# 16_-_PWR_2V5_1V5.net
KiCad netlist of a schematic drawn in Altium Designer
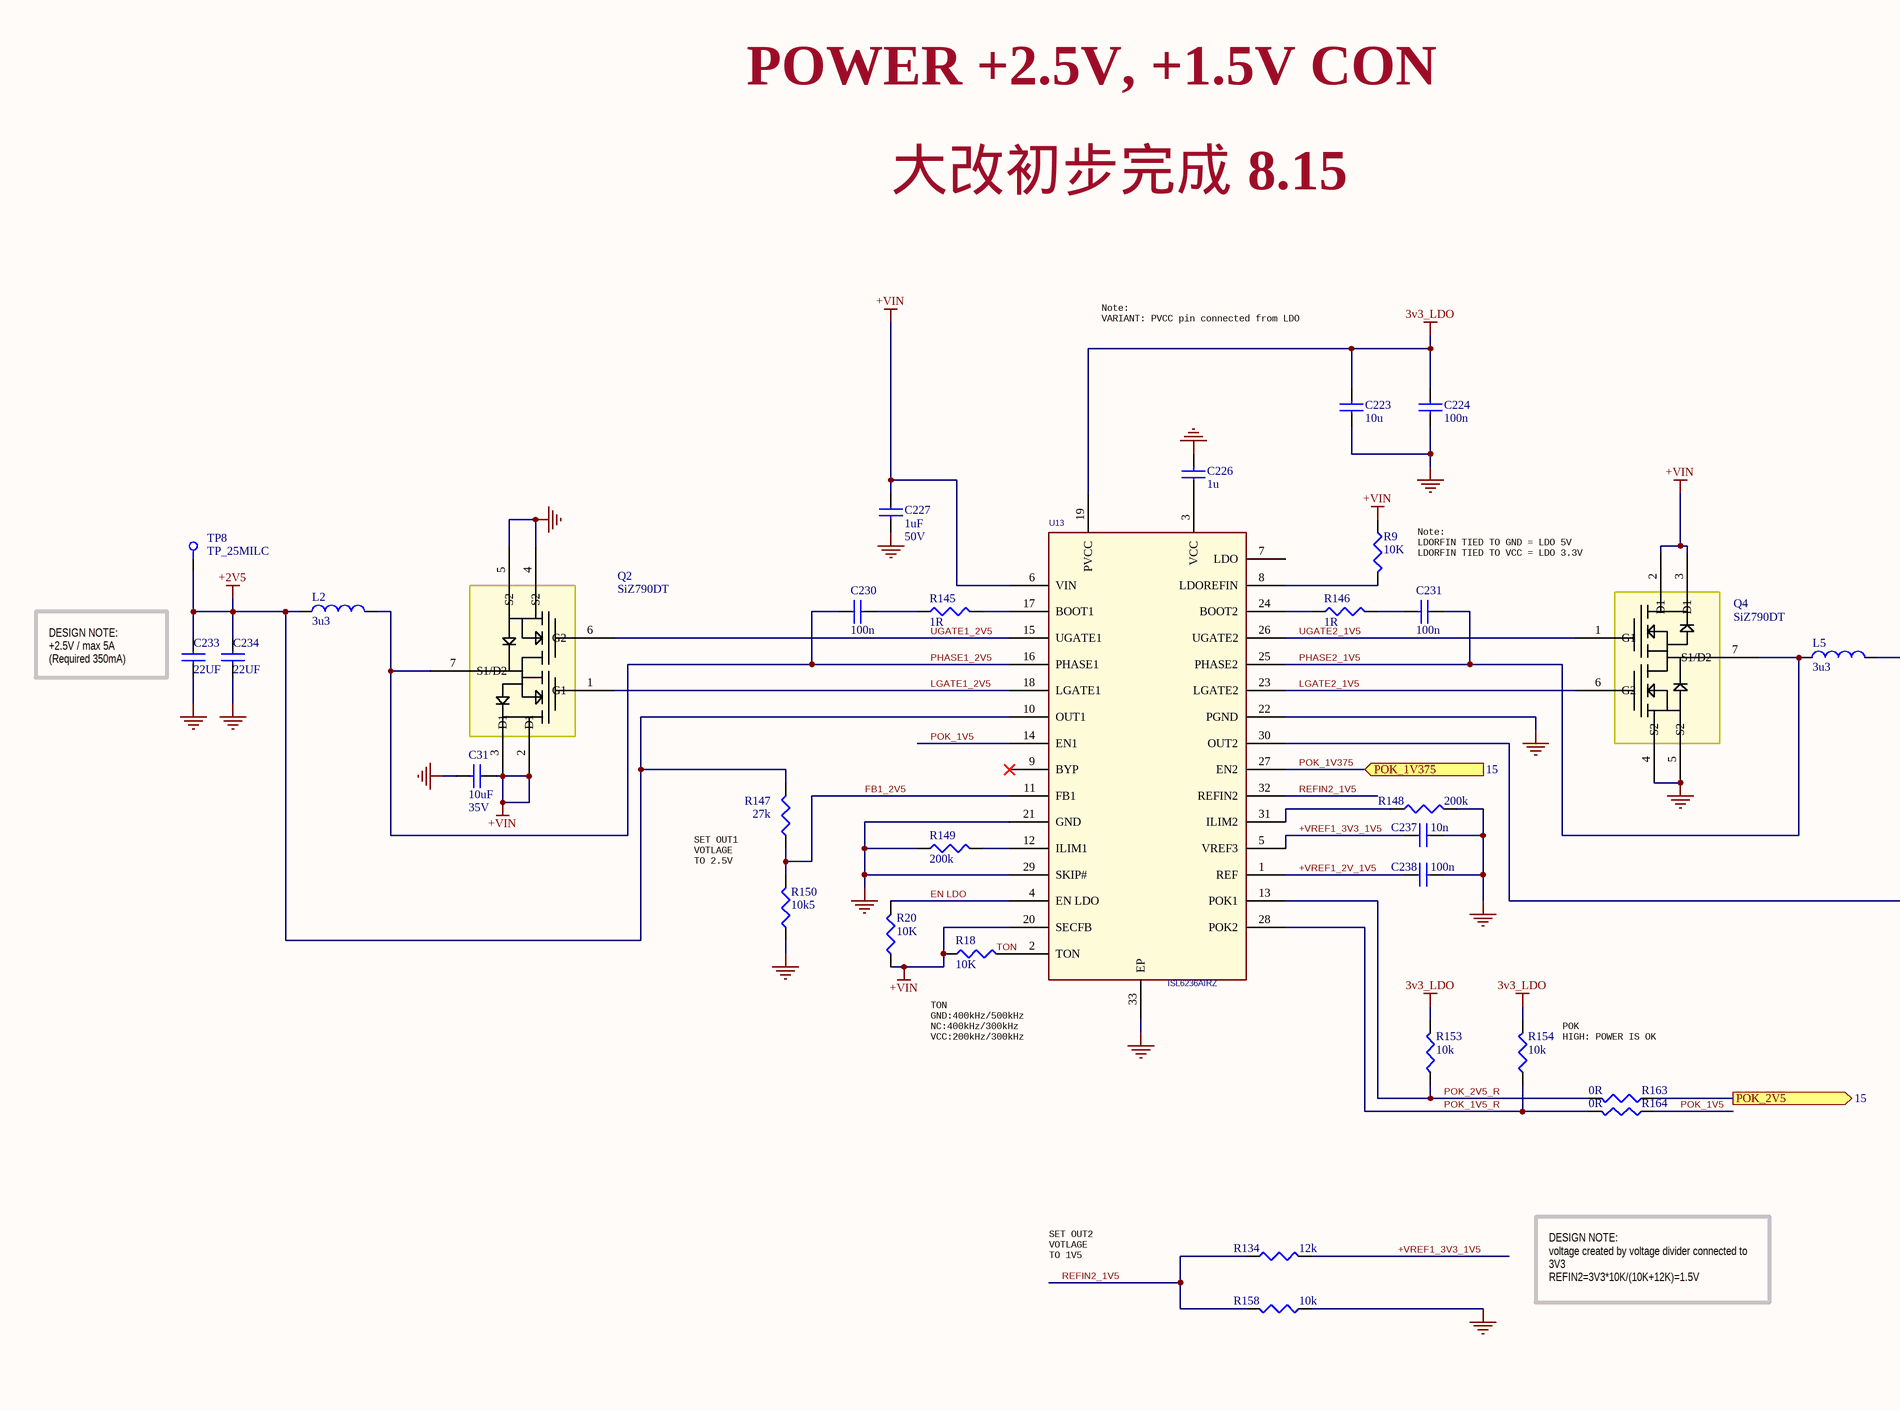
[diagram p0: [16] - PWR 2V5, 1V5.SchDoc, left]
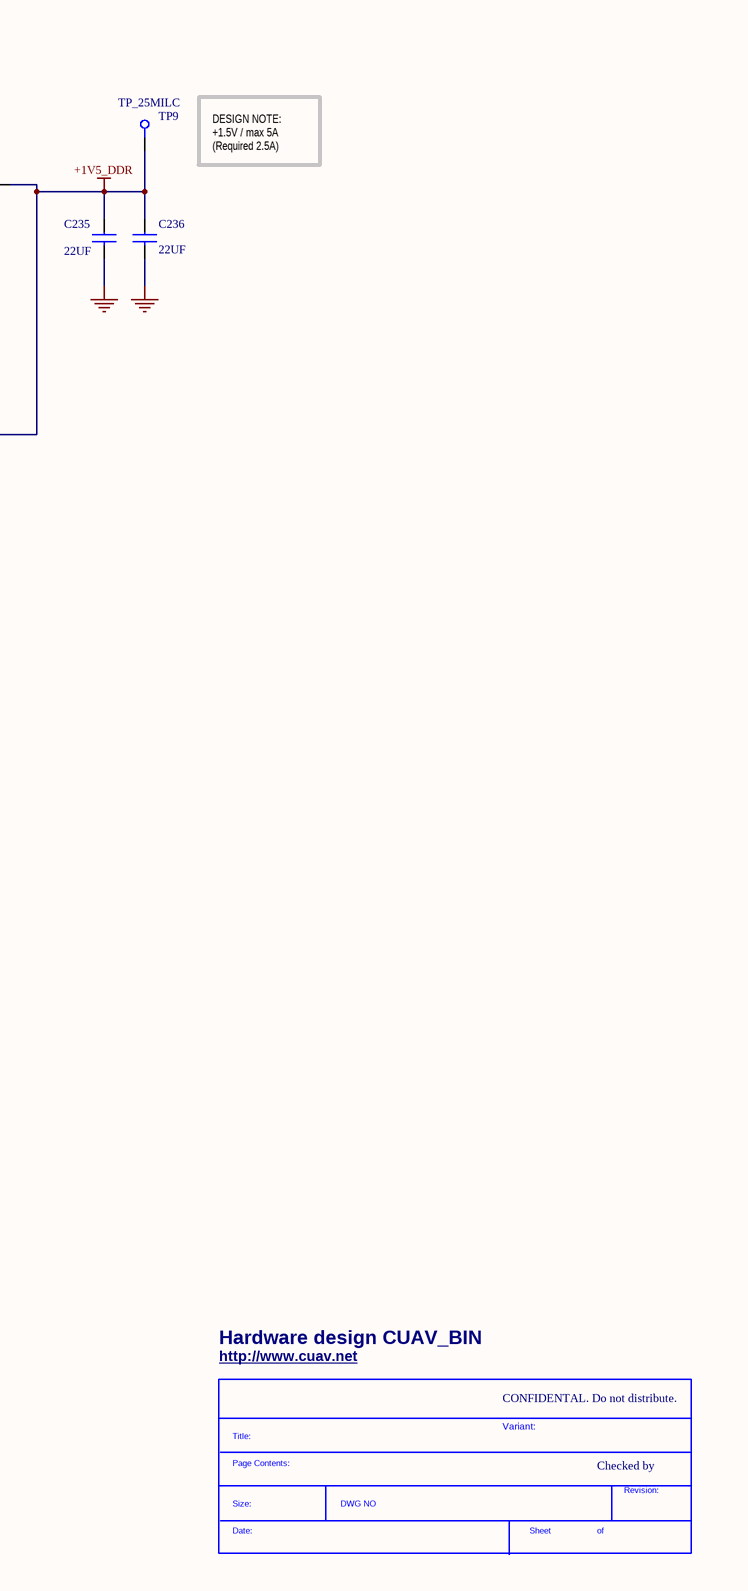
[diagram p1: [16] - PWR 2V5, 1V5.SchDoc, right]

(export (version "E")
  (design (tool "Eeschema 10.0.6"))
  (components
    (comp (ref "*") (value "SDTitleBlock") (libsource (lib "*") (part "SDTitleBlock")))
    (comp (ref "C31")
      (value "10uF")
      (footprint "C1206A")
      (description "CAP CER 10UF 35V X5R 1206")
      (fields
        (field (name "MANUFACTURER") "Murata Electronics North America")
        (field (name "MANUFACTURER PART NUMBER") "GRM31CR6YA106KA12L")
        (field (name "VOLTAGE - RATED") "35V")
      )
      (libsource (lib "Integrated_Library_RF_FEB_2012") (part "GRM31CR6YA106KA12L"))
    )
    (comp (ref "C223")
      (value "10u")
      (footprint "C0603")
      (description "CAP CER 10UF 6.3V X5R 20% 0603")
      (fields
        (field (name "MANUFACTURER") "TDK Corporation")
        (field (name "MANUFACTURER PART NUMBER") "C1608X5R0J106M")
      )
      (libsource (lib "Integrated_Library_RF_FEB_2012") (part "C1608X5R0J106M"))
    )
    (comp (ref "C224")
      (value "100n")
      (footprint "0402CAP")
      (description "CAP CER .10UF 50V X5R 10% 0402")
      (fields
        (field (name "MANUFACTURER") "TDK Corporation")
        (field (name "MANUFACTURER PART NUMBER") "C1005X5R1H104K")
      )
      (libsource (lib "Integrated_Library_RF_FEB_2012") (part "C1005X5R1H104K"))
    )
    (comp (ref "C226")
      (value "1u")
      (footprint "0402CAP")
      (description "CAP CER 1.0UF 16V X5R 0402")
      (fields
        (field (name "MANUFACTURER") "TDK Corporation")
        (field (name "MANUFACTURER PART NUMBER") "C1005X5R1C105K")
      )
      (libsource (lib "Integrated_Library_RF_FEB_2012") (part "C1005X5R1C105K"))
    )
    (comp (ref "C227")
      (value "1uF")
      (footprint "0805CAP")
      (description "CAP CER 1UF 50V X7R 0805")
      (fields
        (field (name "MANUFACTURER") "Murata Electronics North America")
        (field (name "MANUFACTURER PART NUMBER") "GRM21BR71H105KA12L")
        (field (name "VOLTAGE - RATED") "50V")
      )
      (libsource (lib "Integrated_Library_RF_FEB_2012") (part "GRM21BR71H105KA12L"))
    )
    (comp (ref "C230")
      (value "100n")
      (footprint "0402CAP")
      (description "CAP CER .10UF 50V X5R 10% 0402")
      (fields
        (field (name "MANUFACTURER") "TDK Corporation")
        (field (name "MANUFACTURER PART NUMBER") "C1005X5R1H104K")
      )
      (libsource (lib "Integrated_Library_RF_FEB_2012") (part "C1005X5R1H104K"))
    )
    (comp (ref "C231")
      (value "100n")
      (footprint "0402CAP")
      (description "CAP CER .10UF 50V X5R 10% 0402")
      (fields
        (field (name "MANUFACTURER") "TDK Corporation")
        (field (name "MANUFACTURER PART NUMBER") "C1005X5R1H104K")
      )
      (libsource (lib "Integrated_Library_RF_FEB_2012") (part "C1005X5R1H104K"))
    )
    (comp (ref "C233")
      (value "22UF")
      (footprint "C1206A")
      (description "CAP CER 100UF 10V X5R 20% 1206")
      (fields
        (field (name "MANUFACTURER") "TDK Corporation")
        (field (name "MANUFACTURER PART NUMBER") "C3216X5R1A107M")
      )
      (libsource (lib "Integrated_Library_RF_FEB_2012") (part "C3216X5R1A107M"))
    )
    (comp (ref "C234")
      (value "22UF")
      (footprint "C1206A")
      (description "CAP CER 100UF 10V X5R 20% 1206")
      (fields
        (field (name "MANUFACTURER") "TDK Corporation")
        (field (name "MANUFACTURER PART NUMBER") "C3216X5R1A107M")
      )
      (libsource (lib "Integrated_Library_RF_FEB_2012") (part "C3216X5R1A107M"))
    )
    (comp (ref "C235")
      (value "22UF")
      (footprint "C1206")
      (description "CAP CER 100UF 10V X5R 20% 1206")
      (fields
        (field (name "MANUFACTURER") "TDK Corporation")
        (field (name "MANUFACTURER PART NUMBER") "C3216X5R1A107M")
      )
      (libsource (lib "Integrated_Library_RF_FEB_2012") (part "C3216X5R1A107M"))
    )
    (comp (ref "C236")
      (value "22UF")
      (footprint "C1206A")
      (description "CAP CER 100UF 10V X5R 20% 1206")
      (fields
        (field (name "MANUFACTURER") "TDK Corporation")
        (field (name "MANUFACTURER PART NUMBER") "C3216X5R1A107M")
      )
      (libsource (lib "Integrated_Library_RF_FEB_2012") (part "C3216X5R1A107M"))
    )
    (comp (ref "C237")
      (value "10n")
      (footprint "0402CAP")
      (description "CAP CER 10000PF 16V X7R 10% 0402")
      (fields
        (field (name "MANUFACTURER") "TDK Corporation")
        (field (name "MANUFACTURER PART NUMBER") "C1005X7R1C103K")
      )
      (libsource (lib "Integrated_Library_RF_FEB_2012") (part "C1005X7R1C103K"))
    )
    (comp (ref "C238")
      (value "100n")
      (footprint "0402CAP")
      (description "CAP CER .10UF 50V X5R 10% 0402")
      (fields
        (field (name "MANUFACTURER") "TDK Corporation")
        (field (name "MANUFACTURER PART NUMBER") "C1005X5R1H104K")
      )
      (libsource (lib "Integrated_Library_RF_FEB_2012") (part "C1005X5R1H104K"))
    )
    (comp (ref "L2")
      (value "3u3")
      (footprint "6x6_Inductor")
      (description "INDUCTOR POWER 3.3UH 6A SMD")
      (fields
        (field (name "MANUFACTURER") "Vishay Dale")
        (field (name "MANUFACTURER PART NUMBER") "IHLP2525CZER3R3M01")
        (field (name ".CHECKED PCB") "RF")
        (field (name ".CHECKED SCH") "RF")
      )
      (libsource (lib "Integrated_Library_RF_FEB_2012") (part "IHLP2525CZER3R3M01"))
    )
    (comp (ref "L5")
      (value "3u3")
      (footprint "6x6_Inductor")
      (description "INDUCTOR POWER 3.3UH 6A SMD")
      (fields
        (field (name "MANUFACTURER") "Vishay Dale")
        (field (name "MANUFACTURER PART NUMBER") "IHLP2525CZER3R3M01")
        (field (name ".CHECKED PCB") "RF")
        (field (name ".CHECKED SCH") "RF")
      )
      (libsource (lib "Integrated_Library_RF_FEB_2012") (part "IHLP2525CZER3R3M01"))
    )
    (comp (ref "Q2")
      (value "SiZ790DT")
      (footprint "PowerPAIR6 x 3.7")
      (libsource (lib "hack") (part "SiZ790DT"))
    )
    (comp (ref "Q4")
      (value "SiZ790DT")
      (footprint "PowerPAIR6 x 3.7")
      (libsource (lib "hack") (part "SiZ790DT"))
    )
    (comp (ref "R9")
      (value "10K")
      (footprint "R0402")
      (description "RES 0.0 OHM 1/16W 0402 SMD")
      (fields
        (field (name "MANUFACTURER") "Yageo")
        (field (name "MANUFACTURER PART NUMBER") "RC0402JR-070RL")
      )
      (libsource (lib "Integrated_Library_RF_FEB_2012") (part "RC0402JR-070RL"))
    )
    (comp (ref "R18")
      (value "10K")
      (footprint "R0402")
      (description "RES 0.0 OHM 1/16W 0402 SMD")
      (fields
        (field (name "MANUFACTURER") "Yageo")
        (field (name "MANUFACTURER PART NUMBER") "RC0402JR-070RL")
      )
      (libsource (lib "Integrated_Library_RF_FEB_2012") (part "RC0402JR-070RL"))
    )
    (comp (ref "R20")
      (value "10K")
      (footprint "R0402")
      (description "RES 0.0 OHM 1/16W 0402 SMD")
      (fields
        (field (name "MANUFACTURER") "Yageo")
        (field (name "MANUFACTURER PART NUMBER") "RC0402JR-070RL")
      )
      (libsource (lib "Integrated_Library_RF_FEB_2012") (part "RC0402JR-070RL"))
    )
    (comp (ref "R134")
      (value "12k")
      (footprint "R0402")
      (description "RES 12.0K OHM 1/16W 1% 0402 SMD")
      (fields
        (field (name "MANUFACTURER") "Yageo")
        (field (name "MANUFACTURER PART NUMBER") "RC0402FR-0712KL")
      )
      (libsource (lib "Integrated_Library_RF_FEB_2012") (part "RC0402FR-0712KL"))
    )
    (comp (ref "R145")
      (value "1R")
      (footprint "R0402")
      (description "RES 1.00 OHM 1/16W 1% 0402 SM")
      (fields
        (field (name "MANUFACTURER") "Yageo")
        (field (name "MANUFACTURER PART NUMBER") "RC0402FR-071RL")
      )
      (libsource (lib "Integrated_Library_RF_FEB_2012") (part "RC0402FR-071RL"))
    )
    (comp (ref "R146")
      (value "1R")
      (footprint "R0402")
      (description "RES 1.00 OHM 1/16W 1% 0402 SM")
      (fields
        (field (name "MANUFACTURER") "Yageo")
        (field (name "MANUFACTURER PART NUMBER") "RC0402FR-071RL")
      )
      (libsource (lib "Integrated_Library_RF_FEB_2012") (part "RC0402FR-071RL"))
    )
    (comp (ref "R147")
      (value "27k")
      (footprint "R0402")
      (description "RES 27.0K OHM 1/16W 1% 0402 SMD")
      (fields
        (field (name "MANUFACTURER") "Yageo")
        (field (name "MANUFACTURER PART NUMBER") "RC0402FR-0727KL")
        (field (name ".CHECKED PCB") "RF")
        (field (name ".CHECKED SCH") "RF")
      )
      (libsource (lib "Integrated_Library_RF_FEB_2012") (part "RC0402FR-0727KL"))
    )
    (comp (ref "R148")
      (value "200k")
      (footprint "R0402")
      (description "RES 200K OHM 1/16W 1% 0402 SMD")
      (fields
        (field (name "MANUFACTURER") "Yageo")
        (field (name "MANUFACTURER PART NUMBER") "RC0402FR-07200KL")
      )
      (libsource (lib "Integrated_Library_RF_FEB_2012") (part "RC0402FR-07200KL"))
    )
    (comp (ref "R149")
      (value "200k")
      (footprint "R0402")
      (description "RES 200K OHM 1/16W 1% 0402 SMD")
      (fields
        (field (name "MANUFACTURER") "Yageo")
        (field (name "MANUFACTURER PART NUMBER") "RC0402FR-07200KL")
      )
      (libsource (lib "Integrated_Library_RF_FEB_2012") (part "RC0402FR-07200KL"))
    )
    (comp (ref "R150")
      (value "10k5")
      (footprint "R0402")
      (description "RES 10.5K OHM 1/16W 1% 0402 SMD")
      (fields
        (field (name "MANUFACTURER") "Vishay/Dale")
        (field (name "MANUFACTURER PART NUMBER") "CRCW040210K5FKED")
      )
      (libsource (lib "Integrated_Library_RF_FEB_2012") (part "CRCW040210K5FKED"))
    )
    (comp (ref "R153")
      (value "10k")
      (footprint "R0402")
      (description "RES 10.0K OHM 1/16W 1% 0402 SMD")
      (fields
        (field (name "MANUFACTURER") "Yageo")
        (field (name "MANUFACTURER PART NUMBER") "RC0402FR-0710KL")
      )
      (libsource (lib "Integrated_Library_RF_FEB_2012") (part "RC0402FR-0710KL"))
    )
    (comp (ref "R154")
      (value "10k")
      (footprint "R0402")
      (description "RES 10.0K OHM 1/16W 1% 0402 SMD")
      (fields
        (field (name "MANUFACTURER") "Yageo")
        (field (name "MANUFACTURER PART NUMBER") "RC0402FR-0710KL")
      )
      (libsource (lib "Integrated_Library_RF_FEB_2012") (part "RC0402FR-0710KL"))
    )
    (comp (ref "R158")
      (value "10k")
      (footprint "R0402")
      (description "RES 10.0K OHM 1/16W 1% 0402 SMD")
      (fields
        (field (name "MANUFACTURER") "Yageo")
        (field (name "MANUFACTURER PART NUMBER") "RC0402FR-0710KL")
      )
      (libsource (lib "Integrated_Library_RF_FEB_2012") (part "RC0402FR-0710KL"))
    )
    (comp (ref "R163")
      (value "0R")
      (footprint "R0402")
      (description "RES 0.0 OHM 1/16W 0402 SMD")
      (fields
        (field (name "MANUFACTURER") "Yageo")
        (field (name "MANUFACTURER PART NUMBER") "RC0402JR-070RL")
      )
      (libsource (lib "Integrated_Library_RF_FEB_2012") (part "RC0402JR-070RL"))
    )
    (comp (ref "R164")
      (value "0R")
      (footprint "R0402")
      (description "RES 0.0 OHM 1/16W 0402 SMD")
      (fields
        (field (name "MANUFACTURER") "Yageo")
        (field (name "MANUFACTURER PART NUMBER") "RC0402JR-070RL")
      )
      (libsource (lib "Integrated_Library_RF_FEB_2012") (part "RC0402JR-070RL"))
    )
    (comp (ref "TP8")
      (value "TP_25MILC")
      (footprint "TP_25C")
      (description "Test Point 25mil")
      (libsource (lib "Integrated_Library_RF_FEB_2012") (part "TP_25MILC"))
    )
    (comp (ref "TP9")
      (value "TP_25MILC")
      (footprint "TP_25C")
      (description "Test Point 25mil")
      (libsource (lib "Integrated_Library_RF_FEB_2012") (part "TP_25MILC"))
    )
    (comp (ref "U13")
      (value "ISL6236AIRZ")
      (footprint "QFN32_1")
      (description "IC MAIN PWR CTRLR QUAD 32-QFN")
      (fields (field (name "MANUFACTURER") "Intersil"))
      (libsource (lib "Integrated_Library_RF_FEB_2012") (part "ISL6236AIRZ"))
    )
  )
  (nets
    (net (code "1") (name "+1V5_DDR") (class "Default")
      (node (ref "C235") (pin "1") (pinfunction "1_1") (pintype "passive"))
      (node (ref "C236") (pin "1") (pinfunction "1_1") (pintype "passive"))
      (node (ref "L5") (pin "2") (pinfunction "2_2") (pintype "passive"))
      (node (ref "TP9") (pin "1") (pinfunction "1_1") (pintype "passive"))
      (node (ref "U13") (pin "30") (pinfunction "OUT2_30") (pintype "passive"))
    )
    (net (code "2") (name "+2V5") (class "Default")
      (node (ref "C233") (pin "1") (pinfunction "1_1") (pintype "passive"))
      (node (ref "C234") (pin "1") (pinfunction "1_1") (pintype "passive"))
      (node (ref "L2") (pin "1") (pinfunction "1_1") (pintype "passive"))
      (node (ref "R147") (pin "2") (pinfunction "2_2") (pintype "passive"))
      (node (ref "TP8") (pin "1") (pinfunction "1_1") (pintype "passive"))
      (node (ref "U13") (pin "10") (pinfunction "OUT1_10") (pintype "passive"))
    )
    (net (code "3") (name "+VIN") (class "Default")
      (node (ref "C227") (pin "1") (pinfunction "1_1") (pintype "passive"))
      (node (ref "C31") (pin "1") (pinfunction "1_1") (pintype "passive"))
      (node (ref "Q2") (pin "2") (pinfunction "D1_2") (pintype "passive"))
      (node (ref "Q2") (pin "3") (pinfunction "D1_3") (pintype "passive"))
      (node (ref "Q4") (pin "2") (pinfunction "D1_2") (pintype "passive"))
      (node (ref "Q4") (pin "3") (pinfunction "D1_3") (pintype "passive"))
      (node (ref "R18") (pin "1") (pinfunction "1_1") (pintype "passive"))
      (node (ref "R20") (pin "1") (pinfunction "1_1") (pintype "passive"))
      (node (ref "R9") (pin "1") (pinfunction "1_1") (pintype "passive"))
      (node (ref "U13") (pin "20") (pinfunction "SECFB_20") (pintype "passive"))
      (node (ref "U13") (pin "6") (pinfunction "VIN_6") (pintype "passive"))
    )
    (net (code "4") (name "/+VREF1_2V_1V5") (class "Default")
      (node (ref "C238") (pin "1") (pinfunction "1_1") (pintype "passive"))
      (node (ref "U13") (pin "1") (pinfunction "REF_1") (pintype "passive"))
    )
    (net (code "5") (name "/+VREF1_3V3_1V5") (class "Default")
      (node (ref "C237") (pin "1") (pinfunction "1_1") (pintype "passive"))
      (node (ref "R134") (pin "2") (pinfunction "2_2") (pintype "passive"))
      (node (ref "U13") (pin "5") (pinfunction "VREF3_5") (pintype "passive"))
    )
    (net (code "6") (name "/EN LDO") (class "Default")
      (node (ref "R20") (pin "2") (pinfunction "2_2") (pintype "passive"))
      (node (ref "U13") (pin "4") (pinfunction "EN_LDO_4") (pintype "passive"))
    )
    (net (code "7") (name "/FB1_2V5") (class "Default")
      (node (ref "R147") (pin "1") (pinfunction "1_1") (pintype "passive"))
      (node (ref "R150") (pin "2") (pinfunction "2_2") (pintype "passive"))
      (node (ref "U13") (pin "11") (pinfunction "FB1_11") (pintype "passive"))
    )
    (net (code "8") (name "/LGATE1_2V5") (class "Default")
      (node (ref "Q2") (pin "1") (pinfunction "G1_1") (pintype "passive"))
      (node (ref "U13") (pin "18") (pinfunction "LGATE1_18") (pintype "passive"))
    )
    (net (code "9") (name "/LGATE2_1V5") (class "Default")
      (node (ref "Q4") (pin "6") (pinfunction "G2_6") (pintype "passive"))
      (node (ref "U13") (pin "23") (pinfunction "LGATE2_23") (pintype "passive"))
    )
    (net (code "10") (name "/PHASE1_2V5") (class "Default")
      (node (ref "C230") (pin "1") (pinfunction "1_1") (pintype "passive"))
      (node (ref "L2") (pin "2") (pinfunction "2_2") (pintype "passive"))
      (node (ref "Q2") (pin "7") (pinfunction "S1/D2_7") (pintype "passive"))
      (node (ref "U13") (pin "16") (pinfunction "PHASE1_16") (pintype "passive"))
    )
    (net (code "11") (name "/PHASE2_1V5") (class "Default")
      (node (ref "C231") (pin "1") (pinfunction "1_1") (pintype "passive"))
      (node (ref "L5") (pin "1") (pinfunction "1_1") (pintype "passive"))
      (node (ref "Q4") (pin "7") (pinfunction "S1/D2_7") (pintype "passive"))
      (node (ref "U13") (pin "25") (pinfunction "PHASE2_25") (pintype "passive"))
    )
    (net (code "12") (name "/POK_1V5") (class "Default")
      (node (ref "R164") (pin "1") (pinfunction "1_1") (pintype "passive"))
      (node (ref "U13") (pin "14") (pinfunction "EN1_14") (pintype "passive"))
    )
    (net (code "13") (name "/POK_1V5_R") (class "Default")
      (node (ref "R154") (pin "1") (pinfunction "1_1") (pintype "passive"))
      (node (ref "R164") (pin "2") (pinfunction "2_2") (pintype "passive"))
      (node (ref "U13") (pin "28") (pinfunction "POK2_28") (pintype "passive"))
    )
    (net (code "14") (name "/POK_1V375") (class "Default")
      (node (ref "U13") (pin "27") (pinfunction "EN2_27") (pintype "passive"))
    )
    (net (code "15") (name "/POK_2V5") (class "Default")
      (node (ref "R163") (pin "1") (pinfunction "1_1") (pintype "passive"))
    )
    (net (code "16") (name "/POK_2V5_R") (class "Default")
      (node (ref "R153") (pin "1") (pinfunction "1_1") (pintype "passive"))
      (node (ref "R163") (pin "2") (pinfunction "2_2") (pintype "passive"))
      (node (ref "U13") (pin "13") (pinfunction "POK1_13") (pintype "passive"))
    )
    (net (code "17") (name "/REFIN2_1V5") (class "Default")
      (node (ref "R134") (pin "1") (pinfunction "1_1") (pintype "passive"))
      (node (ref "R158") (pin "2") (pinfunction "2_2") (pintype "passive"))
      (node (ref "U13") (pin "32") (pinfunction "REFIN2_32") (pintype "passive"))
    )
    (net (code "19") (name "/UGATE1_2V5") (class "Default")
      (node (ref "Q2") (pin "6") (pinfunction "G2_6") (pintype "passive"))
      (node (ref "U13") (pin "15") (pinfunction "UGATE1_15") (pintype "passive"))
    )
    (net (code "20") (name "/UGATE2_1V5") (class "Default")
      (node (ref "Q4") (pin "1") (pinfunction "G1_1") (pintype "passive"))
      (node (ref "U13") (pin "26") (pinfunction "UGATE2_26") (pintype "passive"))
    )
    (net (code "21") (name "3v3_LDO") (class "Default")
      (node (ref "C223") (pin "1") (pinfunction "1_1") (pintype "passive"))
      (node (ref "C224") (pin "1") (pinfunction "1_1") (pintype "passive"))
      (node (ref "R153") (pin "2") (pinfunction "2_2") (pintype "passive"))
      (node (ref "R154") (pin "2") (pinfunction "2_2") (pintype "passive"))
      (node (ref "U13") (pin "19") (pinfunction "PVCC_19") (pintype "passive"))
    )
    (net (code "22") (name "GND") (class "Default")
      (node (ref "C223") (pin "2") (pinfunction "2_2") (pintype "passive"))
      (node (ref "C224") (pin "2") (pinfunction "2_2") (pintype "passive"))
      (node (ref "C226") (pin "2") (pinfunction "2_2") (pintype "passive"))
      (node (ref "C227") (pin "2") (pinfunction "2_2") (pintype "passive"))
      (node (ref "C233") (pin "2") (pinfunction "2_2") (pintype "passive"))
      (node (ref "C234") (pin "2") (pinfunction "2_2") (pintype "passive"))
      (node (ref "C235") (pin "2") (pinfunction "2_2") (pintype "passive"))
      (node (ref "C236") (pin "2") (pinfunction "2_2") (pintype "passive"))
      (node (ref "C237") (pin "2") (pinfunction "2_2") (pintype "passive"))
      (node (ref "C238") (pin "2") (pinfunction "2_2") (pintype "passive"))
      (node (ref "C31") (pin "2") (pinfunction "2_2") (pintype "passive"))
      (node (ref "Q2") (pin "4") (pinfunction "S2_4") (pintype "passive"))
      (node (ref "Q2") (pin "5") (pinfunction "S2_5") (pintype "passive"))
      (node (ref "Q4") (pin "4") (pinfunction "S2_4") (pintype "passive"))
      (node (ref "Q4") (pin "5") (pinfunction "S2_5") (pintype "passive"))
      (node (ref "R148") (pin "2") (pinfunction "2_2") (pintype "passive"))
      (node (ref "R149") (pin "1") (pinfunction "1_1") (pintype "passive"))
      (node (ref "R150") (pin "1") (pinfunction "1_1") (pintype "passive"))
      (node (ref "R158") (pin "1") (pinfunction "1_1") (pintype "passive"))
      (node (ref "U13") (pin "21") (pinfunction "GND_21") (pintype "passive"))
      (node (ref "U13") (pin "22") (pinfunction "PGND_22") (pintype "passive"))
      (node (ref "U13") (pin "29") (pinfunction "SKIP#_29") (pintype "passive"))
      (node (ref "U13") (pin "33") (pinfunction "EP_33") (pintype "passive"))
    )
    (net (code "23") (name "Net-(C230-Pad2)") (class "Default")
      (node (ref "C230") (pin "2") (pinfunction "2_2") (pintype "passive"))
      (node (ref "R145") (pin "1") (pinfunction "1_1") (pintype "passive"))
    )
    (net (code "24") (name "Net-(C231-Pad2)") (class "Default")
      (node (ref "C231") (pin "2") (pinfunction "2_2") (pintype "passive"))
      (node (ref "R146") (pin "2") (pinfunction "2_2") (pintype "passive"))
    )
    (net (code "25") (name "Net-(U13-BOOT1)") (class "Default")
      (node (ref "R145") (pin "2") (pinfunction "2_2") (pintype "passive"))
      (node (ref "U13") (pin "17") (pinfunction "BOOT1_17") (pintype "passive"))
    )
    (net (code "26") (name "Net-(U13-BOOT2)") (class "Default")
      (node (ref "R146") (pin "1") (pinfunction "1_1") (pintype "passive"))
      (node (ref "U13") (pin "24") (pinfunction "BOOT2_24") (pintype "passive"))
    )
    (net (code "27") (name "Net-(U13-ILIM1)") (class "Default")
      (node (ref "R149") (pin "2") (pinfunction "2_2") (pintype "passive"))
      (node (ref "U13") (pin "12") (pinfunction "ILIM1_12") (pintype "passive"))
    )
    (net (code "28") (name "Net-(U13-ILIM2)") (class "Default")
      (node (ref "R148") (pin "1") (pinfunction "1_1") (pintype "passive"))
      (node (ref "U13") (pin "31") (pinfunction "ILIM2_31") (pintype "passive"))
    )
    (net (code "29") (name "Net-(U13-LDOREFIN)") (class "Default")
      (node (ref "R9") (pin "2") (pinfunction "2_2") (pintype "passive"))
      (node (ref "U13") (pin "8") (pinfunction "LDOREFIN_8") (pintype "passive"))
    )
    (net (code "30") (name "Net-(U13-TON)") (class "Default")
      (node (ref "R18") (pin "2") (pinfunction "2_2") (pintype "passive"))
      (node (ref "U13") (pin "2") (pinfunction "TON_2") (pintype "passive"))
    )
    (net (code "31") (name "Net-(U13-VCC)") (class "Default")
      (node (ref "C226") (pin "1") (pinfunction "1_1") (pintype "passive"))
      (node (ref "U13") (pin "3") (pinfunction "VCC_3") (pintype "passive"))
    )
    (net (code "32") (name "unconnected-(U13-BYP-Pad9)") (class "Default")
      (node (ref "U13") (pin "9") (pinfunction "BYP_9") (pintype "passive+no_connect"))
    )
    (net (code "33") (name "unconnected-(U13-LDO-Pad7)") (class "Default")
      (node (ref "U13") (pin "7") (pinfunction "LDO_7") (pintype "passive"))
    )
  )
)
